# GBA_CleanLight.net
KiCad netlist of a schematic drawn in Altium Designer
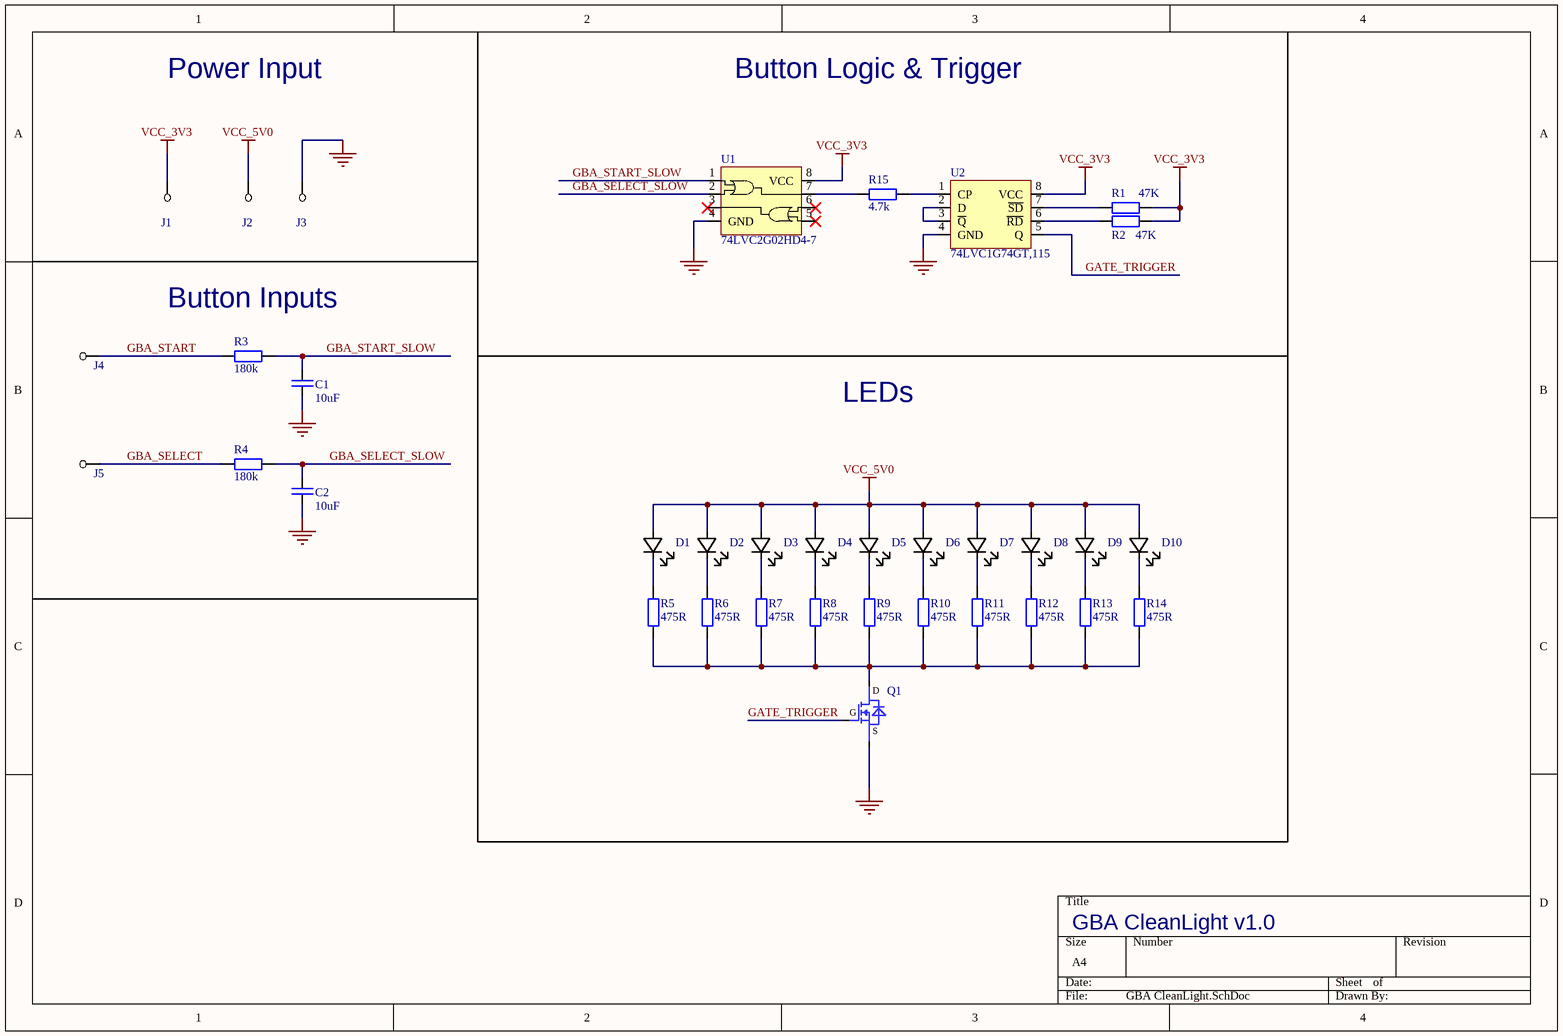
[diagram p0: GBA CleanLight.SchDoc]

(export (version "E")
  (design (tool "Eeschema 10.0.6"))
  (components
    (comp (ref "C1")
      (value "10uF")
      (footprint "C0603")
      (fields
        (field (name "MANUFACTURER") "Murata")
        (field (name "MANUFACTURER PART NUMBER") "GRM188C81C106MA73D")
        (field (name "TOLERANCE") "20%")
      )
      (libsource (lib "Integrated_Library") (part "CAP_10UF_0603"))
    )
    (comp (ref "C2")
      (value "10uF")
      (footprint "C0603")
      (fields
        (field (name "MANUFACTURER") "Murata")
        (field (name "MANUFACTURER PART NUMBER") "GRM188C81C106MA73D")
        (field (name "TOLERANCE") "20%")
      )
      (libsource (lib "Integrated_Library") (part "CAP_10UF_0603"))
    )
    (comp (ref "D1")
      (value "GREEN")
      (footprint "LED0603")
      (description "LED Green Clear 0603")
      (fields
        (field (name "MANUFACTURER") "Lite-On Inc.")
        (field (name "MANUFACTURER PART NUMBER") "LTST-C191KGKT")
      )
      (libsource (lib "Integrated_Library") (part "LED_0603_GREEN"))
    )
    (comp (ref "D2")
      (value "GREEN")
      (footprint "LED0603")
      (description "LED Green Clear 0603")
      (fields
        (field (name "MANUFACTURER") "Lite-On Inc.")
        (field (name "MANUFACTURER PART NUMBER") "LTST-C191KGKT")
      )
      (libsource (lib "Integrated_Library") (part "LED_0603_GREEN"))
    )
    (comp (ref "D3")
      (value "GREEN")
      (footprint "LED0603")
      (description "LED Green Clear 0603")
      (fields
        (field (name "MANUFACTURER") "Lite-On Inc.")
        (field (name "MANUFACTURER PART NUMBER") "LTST-C191KGKT")
      )
      (libsource (lib "Integrated_Library") (part "LED_0603_GREEN"))
    )
    (comp (ref "D4")
      (value "GREEN")
      (footprint "LED0603")
      (description "LED Green Clear 0603")
      (fields
        (field (name "MANUFACTURER") "Lite-On Inc.")
        (field (name "MANUFACTURER PART NUMBER") "LTST-C191KGKT")
      )
      (libsource (lib "Integrated_Library") (part "LED_0603_GREEN"))
    )
    (comp (ref "D5")
      (value "GREEN")
      (footprint "LED0603")
      (description "LED Green Clear 0603")
      (fields
        (field (name "MANUFACTURER") "Lite-On Inc.")
        (field (name "MANUFACTURER PART NUMBER") "LTST-C191KGKT")
      )
      (libsource (lib "Integrated_Library") (part "LED_0603_GREEN"))
    )
    (comp (ref "D6")
      (value "GREEN")
      (footprint "LED0603")
      (description "LED Green Clear 0603")
      (fields
        (field (name "MANUFACTURER") "Lite-On Inc.")
        (field (name "MANUFACTURER PART NUMBER") "LTST-C191KGKT")
      )
      (libsource (lib "Integrated_Library") (part "LED_0603_GREEN"))
    )
    (comp (ref "D7")
      (value "GREEN")
      (footprint "LED0603")
      (description "LED Green Clear 0603")
      (fields
        (field (name "MANUFACTURER") "Lite-On Inc.")
        (field (name "MANUFACTURER PART NUMBER") "LTST-C191KGKT")
      )
      (libsource (lib "Integrated_Library") (part "LED_0603_GREEN"))
    )
    (comp (ref "D8")
      (value "GREEN")
      (footprint "LED0603")
      (description "LED Green Clear 0603")
      (fields
        (field (name "MANUFACTURER") "Lite-On Inc.")
        (field (name "MANUFACTURER PART NUMBER") "LTST-C191KGKT")
      )
      (libsource (lib "Integrated_Library") (part "LED_0603_GREEN"))
    )
    (comp (ref "D9")
      (value "GREEN")
      (footprint "LED0603")
      (description "LED Green Clear 0603")
      (fields
        (field (name "MANUFACTURER") "Lite-On Inc.")
        (field (name "MANUFACTURER PART NUMBER") "LTST-C191KGKT")
      )
      (libsource (lib "Integrated_Library") (part "LED_0603_GREEN"))
    )
    (comp (ref "D10")
      (value "GREEN")
      (footprint "LED0603")
      (description "LED Green Clear 0603")
      (fields
        (field (name "MANUFACTURER") "Lite-On Inc.")
        (field (name "MANUFACTURER PART NUMBER") "LTST-C191KGKT")
      )
      (libsource (lib "Integrated_Library") (part "LED_0603_GREEN"))
    )
    (comp (ref "J1")
      (value "SP")
      (footprint "SP2")
      (description "Solder pad")
      (libsource (lib "Integrated_Library") (part "SP"))
    )
    (comp (ref "J2")
      (value "SP")
      (footprint "SP2")
      (description "Solder pad")
      (libsource (lib "Integrated_Library") (part "SP"))
    )
    (comp (ref "J3")
      (value "SP")
      (footprint "SP2")
      (description "Solder pad")
      (libsource (lib "Integrated_Library") (part "SP"))
    )
    (comp (ref "J4")
      (value "SP")
      (footprint "SP2")
      (description "Solder pad")
      (libsource (lib "Integrated_Library") (part "SP"))
    )
    (comp (ref "J5")
      (value "SP")
      (footprint "SP2")
      (description "Solder pad")
      (libsource (lib "Integrated_Library") (part "SP"))
    )
    (comp (ref "Q1")
      (value "SI1012X-T1-GE3")
      (footprint "SC-89-3")
      (description "MOSFET N-CH 20V 500MA SC89-3")
      (fields (field (name "MANUFACTURER") "Vishay Siliconix"))
      (libsource (lib "Integrated_Library") (part "SI1012X-T1-GE3"))
    )
    (comp (ref "R1")
      (value "47K")
      (footprint "R0402")
      (description "Resistor 47K 1% 0.063W 0402")
      (fields (field (name "MANUFACTURER") "Yageo") (field (name "TOLERANCE") "±1%"))
      (libsource (lib "Integrated_Library") (part "RES_47K_0402"))
    )
    (comp (ref "R2")
      (value "47K")
      (footprint "R0402")
      (description "Resistor 47K 1% 0.063W 0402")
      (fields (field (name "MANUFACTURER") "Yageo") (field (name "TOLERANCE") "±1%"))
      (libsource (lib "Integrated_Library") (part "RES_47K_0402"))
    )
    (comp (ref "R3")
      (value "180k")
      (footprint "R0402")
      (description "Thick Film Resistors 180K OHM 1%")
      (fields
        (field (name "MANUFACTURER") "Yageo")
        (field (name "MANUFACTURER PART NUMBER") "RC0402FR-07180KL")
      )
      (libsource (lib "Integrated_Library") (part "RES_180K_0402"))
    )
    (comp (ref "R4")
      (value "180k")
      (footprint "R0402")
      (description "Thick Film Resistors 180K OHM 1%")
      (fields
        (field (name "MANUFACTURER") "Yageo")
        (field (name "MANUFACTURER PART NUMBER") "RC0402FR-07180KL")
      )
      (libsource (lib "Integrated_Library") (part "RES_180K_0402"))
    )
    (comp (ref "R5")
      (value "475R")
      (footprint "R0402")
      (description "Resistor 475R 0.063W 0402")
      (fields
        (field (name "MANUFACTURER") "Yageo")
        (field (name "MANUFACTURER PART NUMBER") "RC0402FR-07475RL")
      )
      (libsource (lib "Integrated_Library") (part "RES_475R_0402"))
    )
    (comp (ref "R6")
      (value "475R")
      (footprint "R0402")
      (description "Resistor 475R 0.063W 0402")
      (fields
        (field (name "MANUFACTURER") "Yageo")
        (field (name "MANUFACTURER PART NUMBER") "RC0402FR-07475RL")
      )
      (libsource (lib "Integrated_Library") (part "RES_475R_0402"))
    )
    (comp (ref "R7")
      (value "475R")
      (footprint "R0402")
      (description "Resistor 475R 0.063W 0402")
      (fields
        (field (name "MANUFACTURER") "Yageo")
        (field (name "MANUFACTURER PART NUMBER") "RC0402FR-07475RL")
      )
      (libsource (lib "Integrated_Library") (part "RES_475R_0402"))
    )
    (comp (ref "R8")
      (value "475R")
      (footprint "R0402")
      (description "Resistor 475R 0.063W 0402")
      (fields
        (field (name "MANUFACTURER") "Yageo")
        (field (name "MANUFACTURER PART NUMBER") "RC0402FR-07475RL")
      )
      (libsource (lib "Integrated_Library") (part "RES_475R_0402"))
    )
    (comp (ref "R9")
      (value "475R")
      (footprint "R0402")
      (description "Resistor 475R 0.063W 0402")
      (fields
        (field (name "MANUFACTURER") "Yageo")
        (field (name "MANUFACTURER PART NUMBER") "RC0402FR-07475RL")
      )
      (libsource (lib "Integrated_Library") (part "RES_475R_0402"))
    )
    (comp (ref "R10")
      (value "475R")
      (footprint "R0402")
      (description "Resistor 475R 0.063W 0402")
      (fields
        (field (name "MANUFACTURER") "Yageo")
        (field (name "MANUFACTURER PART NUMBER") "RC0402FR-07475RL")
      )
      (libsource (lib "Integrated_Library") (part "RES_475R_0402"))
    )
    (comp (ref "R11")
      (value "475R")
      (footprint "R0402")
      (description "Resistor 475R 0.063W 0402")
      (fields
        (field (name "MANUFACTURER") "Yageo")
        (field (name "MANUFACTURER PART NUMBER") "RC0402FR-07475RL")
      )
      (libsource (lib "Integrated_Library") (part "RES_475R_0402"))
    )
    (comp (ref "R12")
      (value "475R")
      (footprint "R0402")
      (description "Resistor 475R 0.063W 0402")
      (fields
        (field (name "MANUFACTURER") "Yageo")
        (field (name "MANUFACTURER PART NUMBER") "RC0402FR-07475RL")
      )
      (libsource (lib "Integrated_Library") (part "RES_475R_0402"))
    )
    (comp (ref "R13")
      (value "475R")
      (footprint "R0402")
      (description "Resistor 475R 0.063W 0402")
      (fields
        (field (name "MANUFACTURER") "Yageo")
        (field (name "MANUFACTURER PART NUMBER") "RC0402FR-07475RL")
      )
      (libsource (lib "Integrated_Library") (part "RES_475R_0402"))
    )
    (comp (ref "R14")
      (value "475R")
      (footprint "R0402")
      (description "Resistor 475R 0.063W 0402")
      (fields
        (field (name "MANUFACTURER") "Yageo")
        (field (name "MANUFACTURER PART NUMBER") "RC0402FR-07475RL")
      )
      (libsource (lib "Integrated_Library") (part "RES_475R_0402"))
    )
    (comp (ref "R15")
      (value "4.7k")
      (footprint "R0402")
      (description "Resistor 4.7k 0.063W 0402")
      (fields
        (field (name "MANUFACTURER") "Yageo")
        (field (name "MANUFACTURER PART NUMBER") "RT0402BRD074K7L")
      )
      (libsource (lib "Integrated_Library") (part "RES_4K7_0402"))
    )
    (comp (ref "U1")
      (value "74LVC2G02HD4-7")
      (footprint "X2-DFN2010-8 (XSON-8 SOT833-1)")
      (description "74LVC Series 5.5 V 32 mA Surface Mount Dual 2-Input NOR Gate - XFDFN-8")
      (fields (field (name "MANUFACTURER") "Diodes"))
      (libsource (lib "Integrated_Library") (part "74LVC2G02HD4-7"))
    )
    (comp (ref "U2")
      (value "74LVC1G74GT,115")
      (footprint "X2-DFN2010-8 (XSON-8 SOT833-1)")
      (description "74LVC1G74 - Single D-type flip-flop with set and reset; positive-edge trigger")
      (fields (field (name "MANUFACTURER") "Nexperia"))
      (libsource (lib "Integrated_Library") (part "74LVC1G74GT,115"))
    )
  )
  (nets
    (net (code "1") (name "/GATE_TRIGGER") (class "Default")
      (node (ref "Q1") (pin "1") (pinfunction "G_1") (pintype "passive"))
      (node (ref "U2") (pin "5") (pinfunction "Q_5") (pintype "passive"))
    )
    (net (code "2") (name "/GBA_SELECT") (class "Default")
      (node (ref "J5") (pin "1") (pinfunction "1_1") (pintype "passive"))
      (node (ref "R4") (pin "1") (pinfunction "1_1") (pintype "passive"))
    )
    (net (code "3") (name "/GBA_SELECT_SLOW") (class "Default")
      (node (ref "C2") (pin "2") (pinfunction "2_2") (pintype "passive"))
      (node (ref "R4") (pin "2") (pinfunction "2_2") (pintype "passive"))
      (node (ref "U1") (pin "2") (pinfunction "1B_2") (pintype "passive"))
    )
    (net (code "4") (name "/GBA_START") (class "Default")
      (node (ref "J4") (pin "1") (pinfunction "1_1") (pintype "passive"))
      (node (ref "R3") (pin "1") (pinfunction "1_1") (pintype "passive"))
    )
    (net (code "5") (name "/GBA_START_SLOW") (class "Default")
      (node (ref "C1") (pin "2") (pinfunction "2_2") (pintype "passive"))
      (node (ref "R3") (pin "2") (pinfunction "2_2") (pintype "passive"))
      (node (ref "U1") (pin "1") (pinfunction "1A_1") (pintype "passive"))
    )
    (net (code "6") (name "GND") (class "Default")
      (node (ref "C1") (pin "1") (pinfunction "1_1") (pintype "passive"))
      (node (ref "C2") (pin "1") (pinfunction "1_1") (pintype "passive"))
      (node (ref "J3") (pin "1") (pinfunction "1_1") (pintype "passive"))
      (node (ref "Q1") (pin "2") (pinfunction "S_2") (pintype "passive"))
      (node (ref "U1") (pin "4") (pinfunction "GND_4") (pintype "passive"))
      (node (ref "U2") (pin "4") (pinfunction "GND_4") (pintype "passive"))
    )
    (net (code "7") (name "Net-(D1-PadK)") (class "Default")
      (node (ref "D1") (pin "K") (pinfunction "K_K") (pintype "passive"))
      (node (ref "R5") (pin "2") (pinfunction "2_2") (pintype "passive"))
    )
    (net (code "8") (name "Net-(D2-PadK)") (class "Default")
      (node (ref "D2") (pin "K") (pinfunction "K_K") (pintype "passive"))
      (node (ref "R6") (pin "2") (pinfunction "2_2") (pintype "passive"))
    )
    (net (code "9") (name "Net-(D3-PadK)") (class "Default")
      (node (ref "D3") (pin "K") (pinfunction "K_K") (pintype "passive"))
      (node (ref "R7") (pin "2") (pinfunction "2_2") (pintype "passive"))
    )
    (net (code "10") (name "Net-(D4-PadK)") (class "Default")
      (node (ref "D4") (pin "K") (pinfunction "K_K") (pintype "passive"))
      (node (ref "R8") (pin "2") (pinfunction "2_2") (pintype "passive"))
    )
    (net (code "11") (name "Net-(D5-PadK)") (class "Default")
      (node (ref "D5") (pin "K") (pinfunction "K_K") (pintype "passive"))
      (node (ref "R9") (pin "2") (pinfunction "2_2") (pintype "passive"))
    )
    (net (code "12") (name "Net-(D6-PadK)") (class "Default")
      (node (ref "D6") (pin "K") (pinfunction "K_K") (pintype "passive"))
      (node (ref "R10") (pin "2") (pinfunction "2_2") (pintype "passive"))
    )
    (net (code "13") (name "Net-(D7-PadK)") (class "Default")
      (node (ref "D7") (pin "K") (pinfunction "K_K") (pintype "passive"))
      (node (ref "R11") (pin "2") (pinfunction "2_2") (pintype "passive"))
    )
    (net (code "14") (name "Net-(D8-PadK)") (class "Default")
      (node (ref "D8") (pin "K") (pinfunction "K_K") (pintype "passive"))
      (node (ref "R12") (pin "2") (pinfunction "2_2") (pintype "passive"))
    )
    (net (code "15") (name "Net-(D9-PadK)") (class "Default")
      (node (ref "D9") (pin "K") (pinfunction "K_K") (pintype "passive"))
      (node (ref "R13") (pin "2") (pinfunction "2_2") (pintype "passive"))
    )
    (net (code "16") (name "Net-(D10-PadK)") (class "Default")
      (node (ref "D10") (pin "K") (pinfunction "K_K") (pintype "passive"))
      (node (ref "R14") (pin "2") (pinfunction "2_2") (pintype "passive"))
    )
    (net (code "17") (name "Net-(Q1-D)") (class "Default")
      (node (ref "Q1") (pin "3") (pinfunction "D_3") (pintype "passive"))
      (node (ref "R10") (pin "1") (pinfunction "1_1") (pintype "passive"))
      (node (ref "R11") (pin "1") (pinfunction "1_1") (pintype "passive"))
      (node (ref "R12") (pin "1") (pinfunction "1_1") (pintype "passive"))
      (node (ref "R13") (pin "1") (pinfunction "1_1") (pintype "passive"))
      (node (ref "R14") (pin "1") (pinfunction "1_1") (pintype "passive"))
      (node (ref "R5") (pin "1") (pinfunction "1_1") (pintype "passive"))
      (node (ref "R6") (pin "1") (pinfunction "1_1") (pintype "passive"))
      (node (ref "R7") (pin "1") (pinfunction "1_1") (pintype "passive"))
      (node (ref "R8") (pin "1") (pinfunction "1_1") (pintype "passive"))
      (node (ref "R9") (pin "1") (pinfunction "1_1") (pintype "passive"))
    )
    (net (code "18") (name "Net-(U1-1Y)") (class "Default")
      (node (ref "R15") (pin "1") (pinfunction "1_1") (pintype "passive"))
      (node (ref "U1") (pin "7") (pinfunction "1Y_7") (pintype "passive"))
    )
    (net (code "19") (name "Net-(U2-CP)") (class "Default")
      (node (ref "R15") (pin "2") (pinfunction "2_2") (pintype "passive"))
      (node (ref "U2") (pin "1") (pinfunction "CP_1") (pintype "passive"))
    )
    (net (code "20") (name "Net-(U2-D)") (class "Default")
      (node (ref "U2") (pin "2") (pinfunction "D_2") (pintype "passive"))
      (node (ref "U2") (pin "3") (pinfunction "~{Q}_3") (pintype "passive"))
    )
    (net (code "21") (name "Net-(U2-~{RD})") (class "Default")
      (node (ref "R2") (pin "1") (pinfunction "1_1") (pintype "passive"))
      (node (ref "U2") (pin "6") (pinfunction "~{RD}_6") (pintype "passive"))
    )
    (net (code "22") (name "Net-(U2-~{SD})") (class "Default")
      (node (ref "R1") (pin "1") (pinfunction "1_1") (pintype "passive"))
      (node (ref "U2") (pin "7") (pinfunction "~{SD}_7") (pintype "passive"))
    )
    (net (code "23") (name "VCC_3V3") (class "Default")
      (node (ref "J1") (pin "1") (pinfunction "1_1") (pintype "passive"))
      (node (ref "R1") (pin "2") (pinfunction "2_2") (pintype "passive"))
      (node (ref "R2") (pin "2") (pinfunction "2_2") (pintype "passive"))
      (node (ref "U1") (pin "8") (pinfunction "VCC_8") (pintype "passive"))
      (node (ref "U2") (pin "8") (pinfunction "VCC_8") (pintype "passive"))
    )
    (net (code "24") (name "VCC_5V0") (class "Default")
      (node (ref "D1") (pin "A") (pinfunction "A_A") (pintype "passive"))
      (node (ref "D10") (pin "A") (pinfunction "A_A") (pintype "passive"))
      (node (ref "D2") (pin "A") (pinfunction "A_A") (pintype "passive"))
      (node (ref "D3") (pin "A") (pinfunction "A_A") (pintype "passive"))
      (node (ref "D4") (pin "A") (pinfunction "A_A") (pintype "passive"))
      (node (ref "D5") (pin "A") (pinfunction "A_A") (pintype "passive"))
      (node (ref "D6") (pin "A") (pinfunction "A_A") (pintype "passive"))
      (node (ref "D7") (pin "A") (pinfunction "A_A") (pintype "passive"))
      (node (ref "D8") (pin "A") (pinfunction "A_A") (pintype "passive"))
      (node (ref "D9") (pin "A") (pinfunction "A_A") (pintype "passive"))
      (node (ref "J2") (pin "1") (pinfunction "1_1") (pintype "passive"))
    )
    (net (code "25") (name "unconnected-(U1-2A-Pad5)") (class "Default")
      (node (ref "U1") (pin "5") (pinfunction "2A_5") (pintype "passive+no_connect"))
    )
    (net (code "26") (name "unconnected-(U1-2B-Pad6)") (class "Default")
      (node (ref "U1") (pin "6") (pinfunction "2B_6") (pintype "passive+no_connect"))
    )
    (net (code "27") (name "unconnected-(U1-2Y-Pad3)") (class "Default")
      (node (ref "U1") (pin "3") (pinfunction "2Y_3") (pintype "passive+no_connect"))
    )
  )
)
